# Pre_schV2.net
KiCad netlist of a schematic drawn in EAGLE
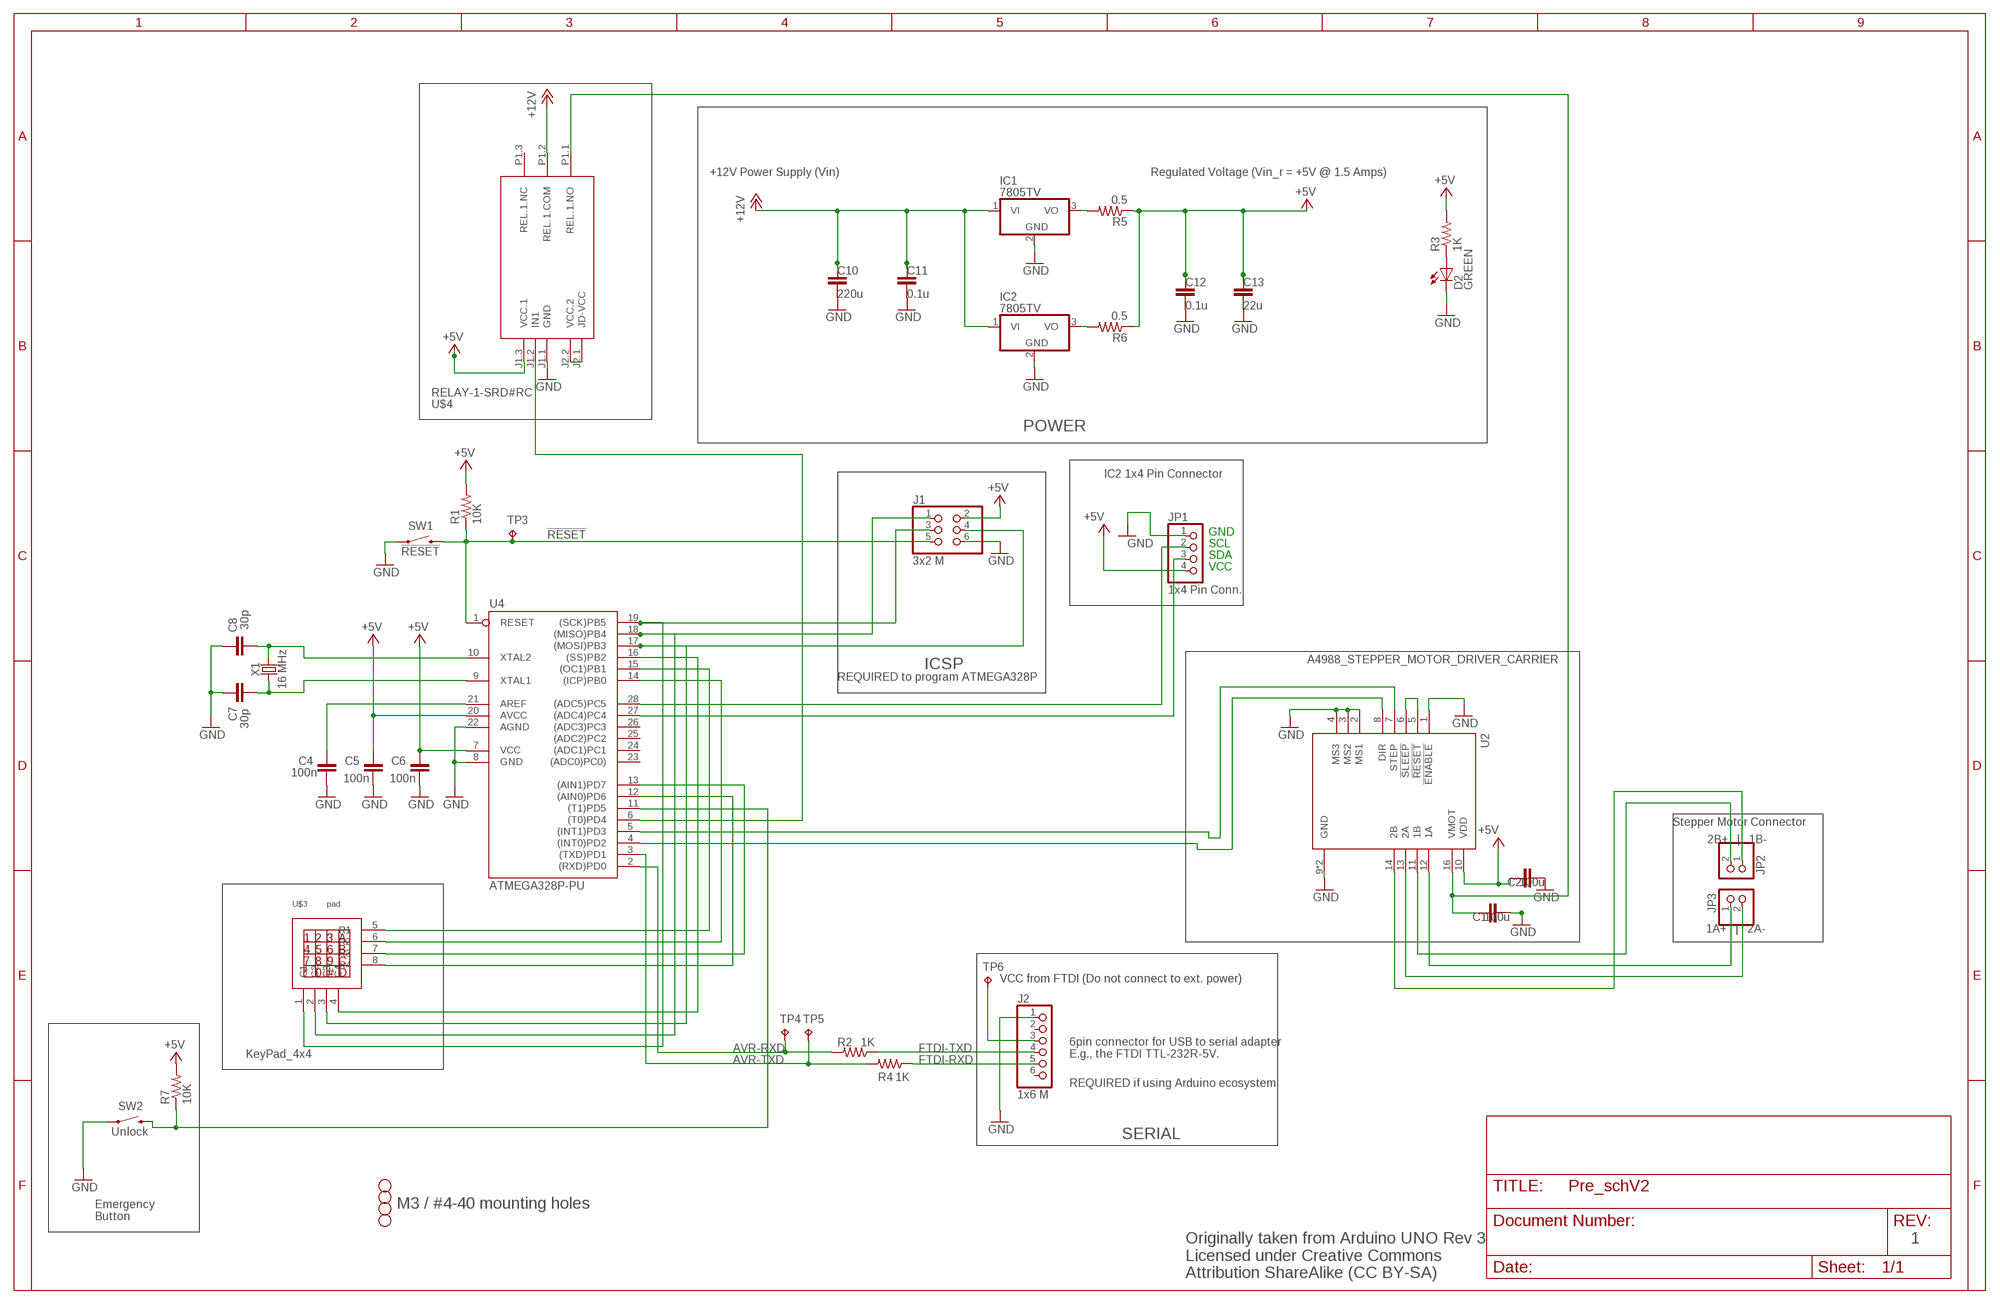
[diagram p0: schematic, sheet 1]

(export (version "E")
  (design (tool "Eeschema 10.0.6"))
  (components
    (comp (ref "C1")
      (value "100u")
      (footprint "eagle-import:C0805K")
      (fields (field (name "MFR") "Samsung") (field (name "MPN") "CL21B104KBCNNNC"))
      (libsource (lib "eagle-import") (part "C-EUC0805K"))
    )
    (comp (ref "C2")
      (value "100u")
      (footprint "eagle-import:C0805K")
      (fields (field (name "MFR") "Samsung") (field (name "MPN") "CL21B104KBCNNNC"))
      (libsource (lib "eagle-import") (part "C-EUC0805K"))
    )
    (comp (ref "C4")
      (value "100n")
      (footprint "eagle-import:C0805K")
      (fields (field (name "MFR") "Samsung") (field (name "MPN") "CL21B104KBCNNNC"))
      (libsource (lib "eagle-import") (part "C-EUC0805K"))
    )
    (comp (ref "C5")
      (value "100n")
      (footprint "eagle-import:C0805K")
      (fields (field (name "MFR") "Samsung") (field (name "MPN") "CL21B104KBCNNNC"))
      (libsource (lib "eagle-import") (part "C-EUC0805K"))
    )
    (comp (ref "C6")
      (value "100n")
      (footprint "eagle-import:C0805K")
      (fields (field (name "MFR") "Samsung") (field (name "MPN") "CL21B104KBCNNNC"))
      (libsource (lib "eagle-import") (part "C-EUC0805K"))
    )
    (comp (ref "C7")
      (value "30p")
      (footprint "eagle-import:C0805K")
      (fields (field (name "MFR") "Samsung") (field (name "MPN") "CL21C180JBANNNC"))
      (libsource (lib "eagle-import") (part "C-EUC0805K"))
    )
    (comp (ref "C8")
      (value "30p")
      (footprint "eagle-import:C0805K")
      (fields (field (name "MFR") "Samsung") (field (name "MPN") "CL21C300JBANNNC"))
      (libsource (lib "eagle-import") (part "C-EUC0805K"))
    )
    (comp (ref "C10")
      (value "220u")
      (footprint "eagle-import:C0805K")
      (fields (field (name "MFR") "Samsung") (field (name "MPN") "CL21B104KBCNNNC"))
      (libsource (lib "eagle-import") (part "C-EUC0805K"))
    )
    (comp (ref "C11")
      (value "0.1u")
      (footprint "eagle-import:C0805K")
      (fields (field (name "MFR") "Samsung") (field (name "MPN") "CL21B104KBCNNNC"))
      (libsource (lib "eagle-import") (part "C-EUC0805K"))
    )
    (comp (ref "C12")
      (value "0.1u")
      (footprint "eagle-import:C0805K")
      (fields (field (name "MFR") "Samsung") (field (name "MPN") "CL21B104KBCNNNC"))
      (libsource (lib "eagle-import") (part "C-EUC0805K"))
    )
    (comp (ref "C13")
      (value "22u")
      (footprint "eagle-import:C0805K")
      (fields (field (name "MFR") "Samsung") (field (name "MPN") "CL21B104KBCNNNC"))
      (libsource (lib "eagle-import") (part "C-EUC0805K"))
    )
    (comp (ref "D2")
      (value "GREEN")
      (footprint "eagle-import:CHIP-LED0805")
      (fields (field (name "MFR") "Würth Elektronik") (field (name "MPN") "150080GS75000"))
      (libsource (lib "eagle-import") (part "LEDCHIP-LED0805"))
    )
    (comp (ref "H1")
      (value "STAND-OFF")
      (footprint "eagle-import:STAND-OFF")
      (libsource (lib "eagle-import") (part "STAND-OFF"))
    )
    (comp (ref "H2")
      (value "STAND-OFF")
      (footprint "eagle-import:STAND-OFF")
      (libsource (lib "eagle-import") (part "STAND-OFF"))
    )
    (comp (ref "H3")
      (value "STAND-OFF")
      (footprint "eagle-import:STAND-OFF")
      (libsource (lib "eagle-import") (part "STAND-OFF"))
    )
    (comp (ref "H4")
      (value "STAND-OFF")
      (footprint "eagle-import:STAND-OFF")
      (libsource (lib "eagle-import") (part "STAND-OFF"))
    )
    (comp (ref "IC1")
      (value "7805TV")
      (footprint "eagle-import:TO220V")
      (libsource (lib "eagle-import") (part "78TV05"))
    )
    (comp (ref "IC2")
      (value "7805TV")
      (footprint "eagle-import:TO220V")
      (libsource (lib "eagle-import") (part "78TV05"))
    )
    (comp (ref "J1")
      (value "3x2 M")
      (footprint "eagle-import:2X03")
      (fields (field (name "MFR") "Harwin") (field (name "MPN") "M20-9980345"))
      (libsource (lib "eagle-import") (part "PINHD-2X3"))
    )
    (comp (ref "J2")
      (value "1x6 M")
      (footprint "eagle-import:1X06")
      (fields (field (name "MFR") "Sullins") (field (name "MPN") "PRPC006SAAN-RC"))
      (libsource (lib "eagle-import") (part "PINHD-1X6"))
    )
    (comp (ref "JP1")
      (value "1x4 Pin Conn.")
      (footprint "eagle-import:1X04")
      (libsource (lib "eagle-import") (part "PINHD-1X4"))
    )
    (comp (ref "JP2")
      (value "2B+ | 1B-")
      (footprint "eagle-import:1X02")
      (libsource (lib "eagle-import") (part "PINHD-1X2"))
    )
    (comp (ref "JP3")
      (value "1A+ | 2A-")
      (footprint "eagle-import:1X02")
      (libsource (lib "eagle-import") (part "PINHD-1X2"))
    )
    (comp (ref "R1")
      (value "10K")
      (footprint "eagle-import:R0805")
      (fields (field (name "MFR") "Yageo") (field (name "MPN") "RC0805FR-0710KL"))
      (libsource (lib "eagle-import") (part "R-US_R0805"))
    )
    (comp (ref "R2")
      (value "1K")
      (footprint "eagle-import:R0805")
      (fields (field (name "MFR") "Yageo") (field (name "MPN") "RC0805FR-071KL"))
      (libsource (lib "eagle-import") (part "R-US_R0805"))
    )
    (comp (ref "R3")
      (value "1K")
      (footprint "eagle-import:R0805")
      (fields (field (name "MFR") "Yageo") (field (name "MPN") "RC0805FR-071KL"))
      (libsource (lib "eagle-import") (part "R-US_R0805"))
    )
    (comp (ref "R4")
      (value "1K")
      (footprint "eagle-import:R0805")
      (fields (field (name "MFR") "Yageo") (field (name "MPN") "RC0805FR-071KL"))
      (libsource (lib "eagle-import") (part "R-US_R0805"))
    )
    (comp (ref "R5")
      (value "0.5")
      (footprint "eagle-import:R0805")
      (fields (field (name "MFR") "Yageo") (field (name "MPN") "RC0805FR-071KL"))
      (libsource (lib "eagle-import") (part "R-US_R0805"))
    )
    (comp (ref "R6")
      (value "0.5")
      (footprint "eagle-import:R0805")
      (fields (field (name "MFR") "Yageo") (field (name "MPN") "RC0805FR-071KL"))
      (libsource (lib "eagle-import") (part "R-US_R0805"))
    )
    (comp (ref "R7")
      (value "10K")
      (footprint "eagle-import:R0805")
      (fields (field (name "MFR") "Yageo") (field (name "MPN") "RC0805FR-0710KL"))
      (libsource (lib "eagle-import") (part "R-US_R0805"))
    )
    (comp (ref "SW1")
      (value "!RESET")
      (footprint "eagle-import:TACTILE_SWITCH_SMD")
      (fields (field (name "MFR") "C&K") (field (name "MPN") "RS-187R05A2-DS MT RT"))
      (libsource (lib "eagle-import") (part "SWITCH-MOMENTARY-2SMD"))
    )
    (comp (ref "SW2")
      (value "Unlock")
      (footprint "eagle-import:TACTILE_SWITCH_SMD")
      (fields (field (name "MFR") "C&K") (field (name "MPN") "RS-187R05A2-DS MT RT"))
      (libsource (lib "eagle-import") (part "SWITCH-MOMENTARY-2SMD"))
    )
    (comp (ref "TP3")
      (value "TPPAD1-13")
      (footprint "eagle-import:P1-13")
      (libsource (lib "eagle-import") (part "TPPAD1-13"))
    )
    (comp (ref "TP4")
      (value "TPPAD1-13")
      (footprint "eagle-import:P1-13")
      (libsource (lib "eagle-import") (part "TPPAD1-13"))
    )
    (comp (ref "TP5")
      (value "TPPAD1-13")
      (footprint "eagle-import:P1-13")
      (libsource (lib "eagle-import") (part "TPPAD1-13"))
    )
    (comp (ref "TP6")
      (value "TPPAD1-13")
      (footprint "eagle-import:P1-13")
      (libsource (lib "eagle-import") (part "TPPAD1-13"))
    )
    (comp (ref "U$3")
      (value "pad")
      (footprint "eagle-import:KEYPAD4X4")
      (libsource (lib "eagle-import") (part "KEYPAD4X4"))
    )
    (comp (ref "U$4")
      (value "RELAY-1-SRD#RC")
      (footprint "eagle-import:RELAY-1-SRD#RC")
      (libsource (lib "eagle-import") (part "RELAY-1-SRD#RC"))
    )
    (comp (ref "U2")
      (value "A4988_STEPPER_MOTOR_DRIVER_CARRIER")
      (footprint "eagle-import:MODULE_A4988_STEPPER_MOTOR_DRIVER_CARRIER")
      (fields (field (name "MF") "Pololu") (field (name "MP") "A4988 STEPPER MOTOR DRIVER CARRIER"))
      (libsource (lib "eagle-import") (part "A4988_STEPPER_MOTOR_DRIVER_CARRIER"))
    )
    (comp (ref "U4")
      (value "ATMEGA328P-PU")
      (footprint "eagle-import:DIL28-3")
      (fields (field (name "MFR") "Microchip"))
      (libsource (lib "eagle-import") (part "ATMEGA328P-PU"))
    )
    (comp (ref "X1")
      (value "16 MHz")
      (footprint "eagle-import:HC49UP")
      (fields (field (name "MFR") "ECS") (field (name "MPN") "ECS-160-18-5PX-TR"))
      (libsource (lib "eagle-import") (part "CRYSTALSMD-HC49UP"))
    )
  )
  (nets
    (net (code "1") (name "+5V") (class "Default")
      (node (ref "C12") (pin "2") (pinfunction "2_2") (pintype "passive"))
      (node (ref "C13") (pin "2") (pinfunction "2_2") (pintype "passive"))
      (node (ref "C2") (pin "2") (pinfunction "2_2") (pintype "passive"))
      (node (ref "C5") (pin "2") (pinfunction "2_2") (pintype "passive"))
      (node (ref "C6") (pin "2") (pinfunction "2_2") (pintype "passive"))
      (node (ref "J1") (pin "2") (pinfunction "2_2") (pintype "passive"))
      (node (ref "JP1") (pin "4") (pinfunction "4_4") (pintype "passive"))
      (node (ref "R1") (pin "2") (pinfunction "2_2") (pintype "passive"))
      (node (ref "R3") (pin "2") (pinfunction "2_2") (pintype "passive"))
      (node (ref "R5") (pin "1") (pinfunction "1_1") (pintype "passive"))
      (node (ref "R6") (pin "1") (pinfunction "1_1") (pintype "passive"))
      (node (ref "R7") (pin "2") (pinfunction "2_2") (pintype "passive"))
      (node (ref "U$4") (pin "J1.3") (pinfunction "VCC.1_J1.3") (pintype "power_in"))
      (node (ref "U2") (pin "10") (pinfunction "VDD_10") (pintype "power_in"))
      (node (ref "U4") (pin "20") (pinfunction "AVCC_20") (pintype "power_in"))
      (node (ref "U4") (pin "7") (pinfunction "VCC_7") (pintype "power_in"))
    )
    (net (code "2") (name "+12V") (class "Default")
      (node (ref "C10") (pin "2") (pinfunction "2_2") (pintype "passive"))
      (node (ref "C11") (pin "2") (pinfunction "2_2") (pintype "passive"))
      (node (ref "IC1") (pin "1") (pinfunction "VI_1") (pintype "input"))
      (node (ref "IC2") (pin "1") (pinfunction "VI_1") (pintype "input"))
      (node (ref "U$4") (pin "P1.2") (pinfunction "REL.1.COM_P1.2") (pintype "bidirectional"))
    )
    (net (code "3") (name "/AVR-RXD") (class "Default")
      (node (ref "R2") (pin "2") (pinfunction "2_2") (pintype "passive"))
      (node (ref "TP4") (pin "TP") (pinfunction "TP_TP") (pintype "input"))
      (node (ref "U4") (pin "2") (pinfunction "(RXD)PD0_2") (pintype "bidirectional"))
    )
    (net (code "4") (name "/AVR-TXD") (class "Default")
      (node (ref "R4") (pin "2") (pinfunction "2_2") (pintype "passive"))
      (node (ref "TP5") (pin "TP") (pinfunction "TP_TP") (pintype "input"))
      (node (ref "U4") (pin "3") (pinfunction "(TXD)PD1_3") (pintype "bidirectional"))
    )
    (net (code "5") (name "/FTDI-RXD") (class "Default")
      (node (ref "J2") (pin "5") (pinfunction "5_5") (pintype "passive"))
      (node (ref "R4") (pin "1") (pinfunction "1_1") (pintype "passive"))
    )
    (net (code "6") (name "/FTDI-TXD") (class "Default")
      (node (ref "J2") (pin "4") (pinfunction "4_4") (pintype "passive"))
      (node (ref "R2") (pin "1") (pinfunction "1_1") (pintype "passive"))
    )
    (net (code "7") (name "/~{RESET}") (class "Default")
      (node (ref "J1") (pin "5") (pinfunction "5_5") (pintype "passive"))
      (node (ref "R1") (pin "1") (pinfunction "1_1") (pintype "passive"))
      (node (ref "SW1") (pin "3") (pinfunction "2_3") (pintype "passive"))
      (node (ref "TP3") (pin "TP") (pinfunction "TP_TP") (pintype "input"))
      (node (ref "U4") (pin "1") (pinfunction "RESET_1") (pintype "input"))
    )
    (net (code "8") (name "GND") (class "Default")
      (node (ref "C1") (pin "1") (pinfunction "1_1") (pintype "passive"))
      (node (ref "C10") (pin "1") (pinfunction "1_1") (pintype "passive"))
      (node (ref "C11") (pin "1") (pinfunction "1_1") (pintype "passive"))
      (node (ref "C12") (pin "1") (pinfunction "1_1") (pintype "passive"))
      (node (ref "C13") (pin "1") (pinfunction "1_1") (pintype "passive"))
      (node (ref "C2") (pin "1") (pinfunction "1_1") (pintype "passive"))
      (node (ref "C4") (pin "1") (pinfunction "1_1") (pintype "passive"))
      (node (ref "C5") (pin "1") (pinfunction "1_1") (pintype "passive"))
      (node (ref "C6") (pin "1") (pinfunction "1_1") (pintype "passive"))
      (node (ref "C7") (pin "2") (pinfunction "2_2") (pintype "passive"))
      (node (ref "C8") (pin "2") (pinfunction "2_2") (pintype "passive"))
      (node (ref "D2") (pin "C") (pinfunction "C_C") (pintype "passive"))
      (node (ref "IC1") (pin "2") (pinfunction "GND_2") (pintype "passive"))
      (node (ref "IC2") (pin "2") (pinfunction "GND_2") (pintype "passive"))
      (node (ref "J1") (pin "6") (pinfunction "6_6") (pintype "passive"))
      (node (ref "J2") (pin "1") (pinfunction "1_1") (pintype "passive"))
      (node (ref "JP1") (pin "1") (pinfunction "1_1") (pintype "passive"))
      (node (ref "SW1") (pin "1") (pinfunction "1_1") (pintype "passive"))
      (node (ref "SW2") (pin "1") (pinfunction "1_1") (pintype "passive"))
      (node (ref "U$4") (pin "J1.1") (pinfunction "GND_J1.1") (pintype "power_in"))
      (node (ref "U2") (pin "1") (pinfunction "~{ENABLE}_1") (pintype "input"))
      (node (ref "U2") (pin "15") (pinfunction "GND_15") (pintype "power_in"))
      (node (ref "U2") (pin "2") (pinfunction "MS1_2") (pintype "input"))
      (node (ref "U2") (pin "3") (pinfunction "MS2_3") (pintype "input"))
      (node (ref "U2") (pin "4") (pinfunction "MS3_4") (pintype "input"))
      (node (ref "U2") (pin "9") (pinfunction "GND_9") (pintype "power_in"))
      (node (ref "U4") (pin "22") (pinfunction "AGND_22") (pintype "power_in"))
      (node (ref "U4") (pin "8") (pinfunction "GND_8") (pintype "power_in"))
    )
    (net (code "9") (name "Net-(D2-PadA)") (class "Default")
      (node (ref "D2") (pin "A") (pinfunction "A_A") (pintype "passive"))
      (node (ref "R3") (pin "1") (pinfunction "1_1") (pintype "passive"))
    )
    (net (code "10") (name "Net-(IC1-VO)") (class "Default")
      (node (ref "IC1") (pin "3") (pinfunction "VO_3") (pintype "passive"))
      (node (ref "R5") (pin "2") (pinfunction "2_2") (pintype "passive"))
    )
    (net (code "11") (name "Net-(IC2-VO)") (class "Default")
      (node (ref "IC2") (pin "3") (pinfunction "VO_3") (pintype "passive"))
      (node (ref "R6") (pin "2") (pinfunction "2_2") (pintype "passive"))
    )
    (net (code "12") (name "Net-(J2-Pad3)") (class "Default")
      (node (ref "J2") (pin "3") (pinfunction "3_3") (pintype "passive"))
      (node (ref "TP6") (pin "TP") (pinfunction "TP_TP") (pintype "input"))
    )
    (net (code "13") (name "Net-(SW2-2)") (class "Default")
      (node (ref "R7") (pin "1") (pinfunction "1_1") (pintype "passive"))
      (node (ref "SW2") (pin "3") (pinfunction "2_3") (pintype "passive"))
      (node (ref "U4") (pin "11") (pinfunction "(T1)PD5_11") (pintype "bidirectional"))
    )
    (net (code "14") (name "Net-(U$3-C1)") (class "Default")
      (node (ref "J1") (pin "3") (pinfunction "3_3") (pintype "passive"))
      (node (ref "U$3") (pin "1") (pinfunction "C1_1") (pintype "bidirectional"))
      (node (ref "U4") (pin "19") (pinfunction "(SCK)PB5_19") (pintype "bidirectional"))
    )
    (net (code "15") (name "Net-(U$3-C2)") (class "Default")
      (node (ref "J1") (pin "1") (pinfunction "1_1") (pintype "passive"))
      (node (ref "U$3") (pin "2") (pinfunction "C2_2") (pintype "bidirectional"))
      (node (ref "U4") (pin "18") (pinfunction "(MISO)PB4_18") (pintype "bidirectional"))
    )
    (net (code "16") (name "Net-(U$3-C3)") (class "Default")
      (node (ref "J1") (pin "4") (pinfunction "4_4") (pintype "passive"))
      (node (ref "U$3") (pin "3") (pinfunction "C3_3") (pintype "bidirectional"))
      (node (ref "U4") (pin "17") (pinfunction "(MOSI)PB3_17") (pintype "bidirectional"))
    )
    (net (code "17") (name "Net-(U$3-C4)") (class "Default")
      (node (ref "U$3") (pin "4") (pinfunction "C4_4") (pintype "bidirectional"))
      (node (ref "U4") (pin "16") (pinfunction "(SS)PB2_16") (pintype "bidirectional"))
    )
    (net (code "18") (name "Net-(U$3-R1)") (class "Default")
      (node (ref "U$3") (pin "5") (pinfunction "R1_5") (pintype "bidirectional"))
      (node (ref "U4") (pin "15") (pinfunction "(OC1)PB1_15") (pintype "bidirectional"))
    )
    (net (code "19") (name "Net-(U$3-R2)") (class "Default")
      (node (ref "U$3") (pin "6") (pinfunction "R2_6") (pintype "bidirectional"))
      (node (ref "U4") (pin "14") (pinfunction "(ICP)PB0_14") (pintype "bidirectional"))
    )
    (net (code "20") (name "Net-(U$3-R3)") (class "Default")
      (node (ref "U$3") (pin "7") (pinfunction "R3_7") (pintype "bidirectional"))
      (node (ref "U4") (pin "13") (pinfunction "(AIN1)PD7_13") (pintype "bidirectional"))
    )
    (net (code "21") (name "Net-(U$3-R4)") (class "Default")
      (node (ref "U$3") (pin "8") (pinfunction "R4_8") (pintype "bidirectional"))
      (node (ref "U4") (pin "12") (pinfunction "(AIN0)PD6_12") (pintype "bidirectional"))
    )
    (net (code "22") (name "Net-(U$4-IN1)") (class "Default")
      (node (ref "U$4") (pin "J1.2") (pinfunction "IN1_J1.2") (pintype "bidirectional"))
      (node (ref "U4") (pin "6") (pinfunction "(T0)PD4_6") (pintype "bidirectional"))
    )
    (net (code "23") (name "Net-(U$4-JD-VCC)") (class "Default")
      (node (ref "U$4") (pin "J2.1") (pinfunction "JD-VCC_J2.1") (pintype "bidirectional"))
      (node (ref "U$4") (pin "J2.2") (pinfunction "VCC.2_J2.2") (pintype "power_in"))
    )
    (net (code "24") (name "Net-(U$4-REL.1.NO)") (class "Default")
      (node (ref "C1") (pin "2") (pinfunction "2_2") (pintype "passive"))
      (node (ref "U$4") (pin "P1.1") (pinfunction "REL.1.NO_P1.1") (pintype "bidirectional"))
      (node (ref "U2") (pin "16") (pinfunction "VMOT_16") (pintype "power_in"))
    )
    (net (code "25") (name "Net-(U2-1A)") (class "Default")
      (node (ref "JP3") (pin "1") (pinfunction "1_1") (pintype "passive"))
      (node (ref "U2") (pin "12") (pinfunction "1A_12") (pintype "output"))
    )
    (net (code "26") (name "Net-(U2-1B)") (class "Default")
      (node (ref "JP2") (pin "2") (pinfunction "2_2") (pintype "passive"))
      (node (ref "U2") (pin "11") (pinfunction "1B_11") (pintype "output"))
    )
    (net (code "27") (name "Net-(U2-2A)") (class "Default")
      (node (ref "JP3") (pin "2") (pinfunction "2_2") (pintype "passive"))
      (node (ref "U2") (pin "13") (pinfunction "2A_13") (pintype "output"))
    )
    (net (code "28") (name "Net-(U2-2B)") (class "Default")
      (node (ref "JP2") (pin "1") (pinfunction "1_1") (pintype "passive"))
      (node (ref "U2") (pin "14") (pinfunction "2B_14") (pintype "output"))
    )
    (net (code "29") (name "Net-(U2-DIR)") (class "Default")
      (node (ref "U2") (pin "8") (pinfunction "DIR_8") (pintype "input"))
      (node (ref "U4") (pin "4") (pinfunction "(INT0)PD2_4") (pintype "bidirectional"))
    )
    (net (code "30") (name "Net-(U2-STEP)") (class "Default")
      (node (ref "U2") (pin "7") (pinfunction "STEP_7") (pintype "input"))
      (node (ref "U4") (pin "5") (pinfunction "(INT1)PD3_5") (pintype "bidirectional"))
    )
    (net (code "31") (name "Net-(U2-~{RESET})") (class "Default")
      (node (ref "U2") (pin "5") (pinfunction "~{RESET}_5") (pintype "input"))
      (node (ref "U2") (pin "6") (pinfunction "~{SLEEP}_6") (pintype "input"))
    )
    (net (code "32") (name "Net-(U4-(ADC4)PC4)") (class "Default")
      (node (ref "JP1") (pin "3") (pinfunction "3_3") (pintype "passive"))
      (node (ref "U4") (pin "27") (pinfunction "(ADC4)PC4_27") (pintype "bidirectional"))
    )
    (net (code "33") (name "Net-(U4-(ADC5)PC5)") (class "Default")
      (node (ref "JP1") (pin "2") (pinfunction "2_2") (pintype "passive"))
      (node (ref "U4") (pin "28") (pinfunction "(ADC5)PC5_28") (pintype "bidirectional"))
    )
    (net (code "34") (name "Net-(U4-AREF)") (class "Default")
      (node (ref "C4") (pin "2") (pinfunction "2_2") (pintype "passive"))
      (node (ref "U4") (pin "21") (pinfunction "AREF_21") (pintype "passive"))
    )
    (net (code "35") (name "Net-(U4-XTAL1)") (class "Default")
      (node (ref "C7") (pin "1") (pinfunction "1_1") (pintype "passive"))
      (node (ref "U4") (pin "9") (pinfunction "XTAL1_9") (pintype "bidirectional"))
      (node (ref "X1") (pin "1") (pinfunction "1_1") (pintype "passive"))
    )
    (net (code "36") (name "Net-(U4-XTAL2)") (class "Default")
      (node (ref "C8") (pin "1") (pinfunction "1_1") (pintype "passive"))
      (node (ref "U4") (pin "10") (pinfunction "XTAL2_10") (pintype "bidirectional"))
      (node (ref "X1") (pin "2") (pinfunction "2_2") (pintype "passive"))
    )
    (net (code "37") (name "unconnected-(J2-Pad2)") (class "Default")
      (node (ref "J2") (pin "2") (pinfunction "2_2") (pintype "passive"))
    )
    (net (code "38") (name "unconnected-(J2-Pad6)") (class "Default")
      (node (ref "J2") (pin "6") (pinfunction "6_6") (pintype "passive"))
    )
    (net (code "39") (name "unconnected-(U$4-REL.1.NC-PadP1.3)") (class "Default")
      (node (ref "U$4") (pin "P1.3") (pinfunction "REL.1.NC_P1.3") (pintype "bidirectional"))
    )
    (net (code "40") (name "unconnected-(U4-(ADC0)PC0)-Pad23)") (class "Default")
      (node (ref "U4") (pin "23") (pinfunction "(ADC0)PC0)_23") (pintype "bidirectional"))
    )
    (net (code "41") (name "unconnected-(U4-(ADC1)PC1-Pad24)") (class "Default")
      (node (ref "U4") (pin "24") (pinfunction "(ADC1)PC1_24") (pintype "bidirectional"))
    )
    (net (code "42") (name "unconnected-(U4-(ADC2)PC2-Pad25)") (class "Default")
      (node (ref "U4") (pin "25") (pinfunction "(ADC2)PC2_25") (pintype "bidirectional"))
    )
    (net (code "43") (name "unconnected-(U4-(ADC3)PC3-Pad26)") (class "Default")
      (node (ref "U4") (pin "26") (pinfunction "(ADC3)PC3_26") (pintype "bidirectional"))
    )
  )
)
